# ForceAssistHandBrd.net
KiCad netlist of a schematic drawn in EAGLE
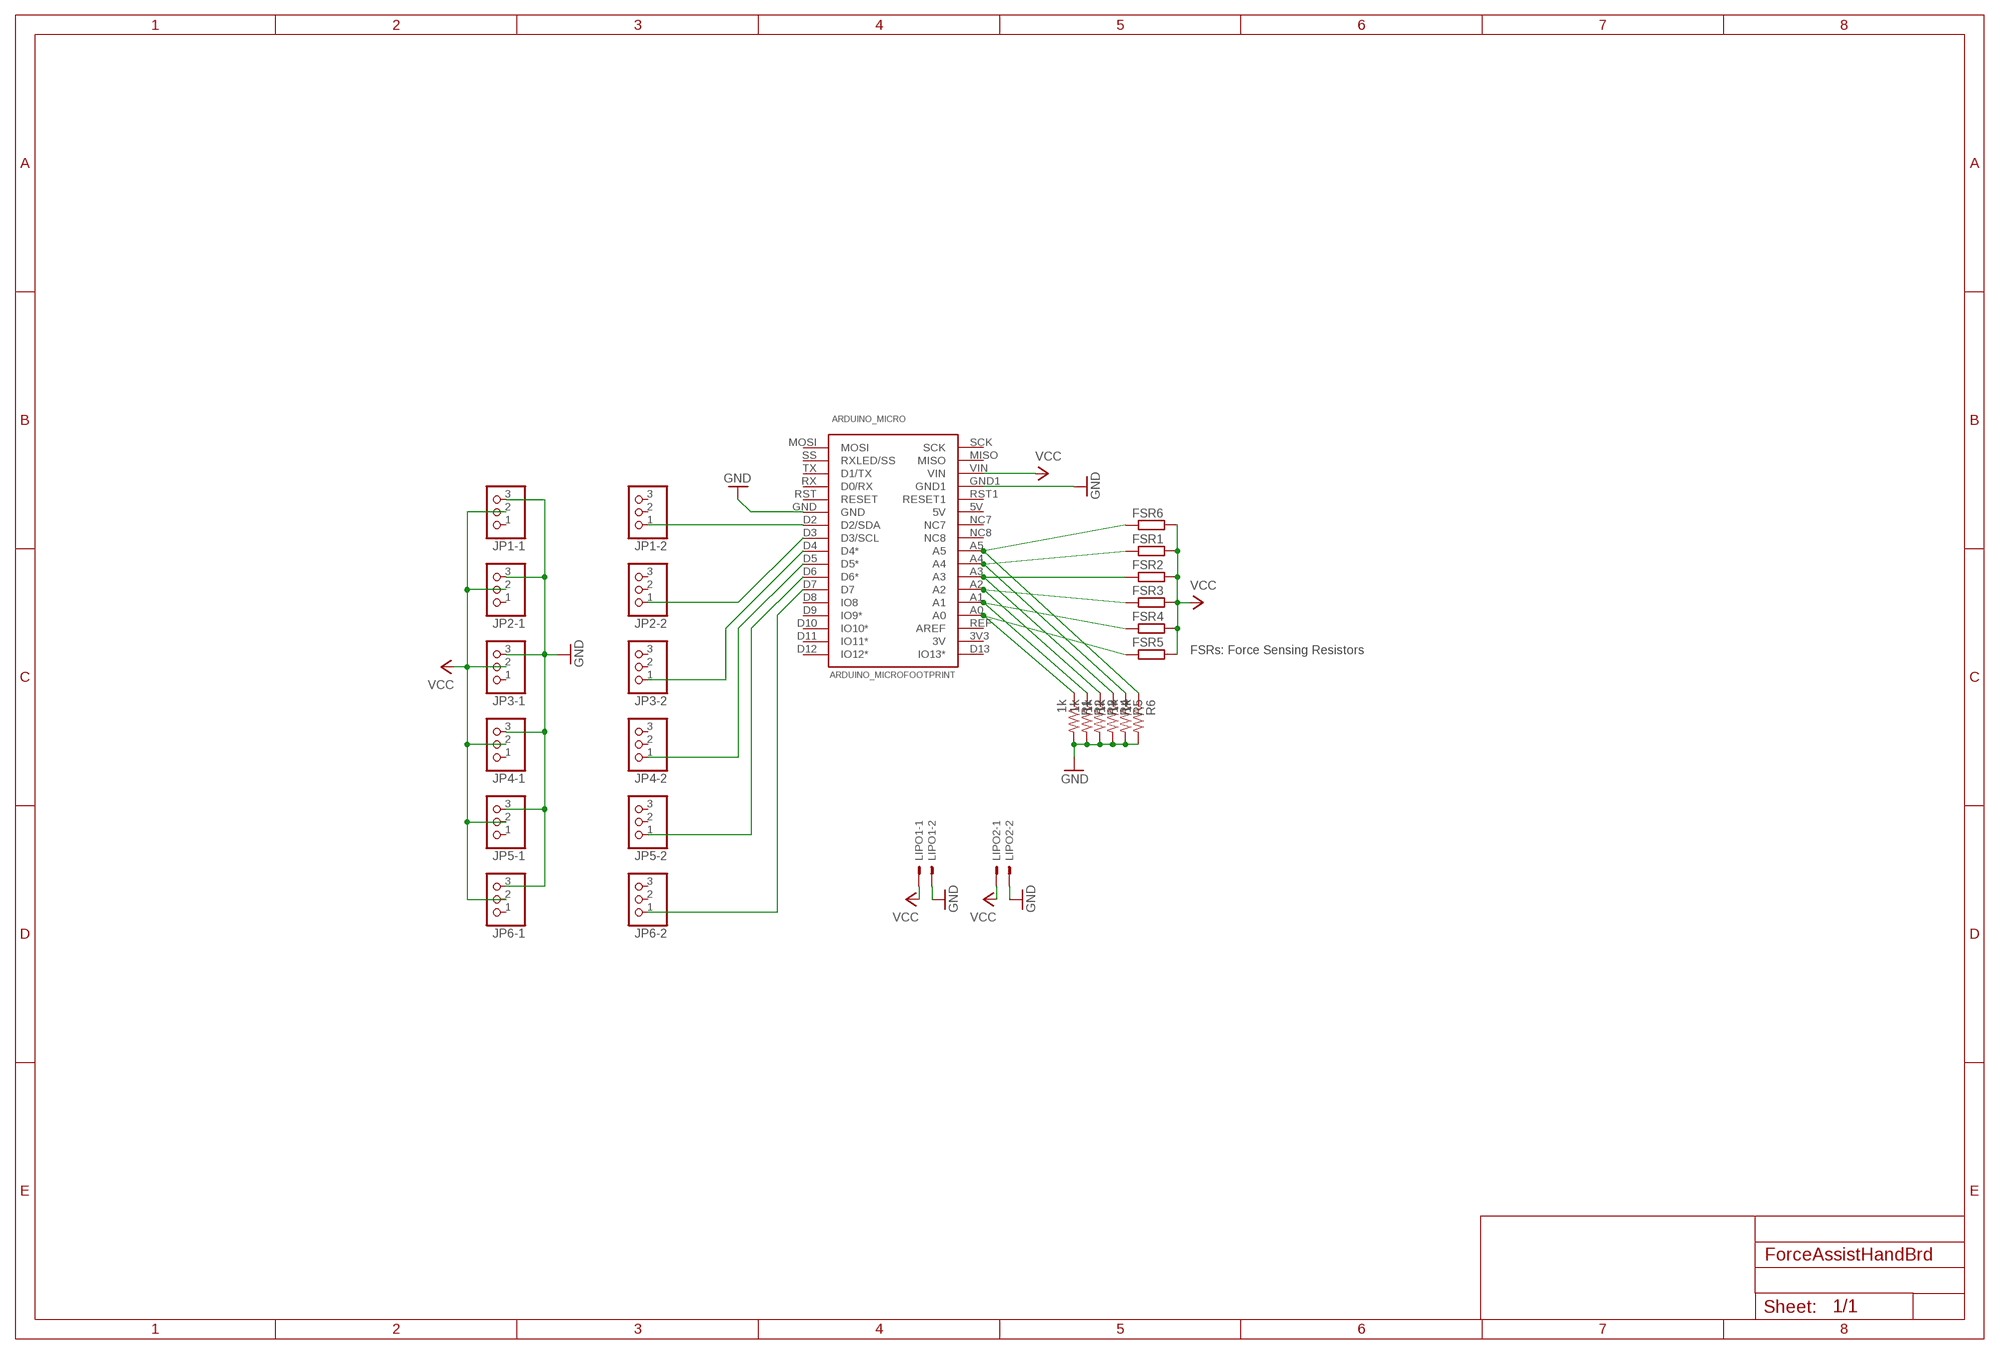
[diagram p0: schematic, sheet 1]

(export (version "E")
  (design (tool "Eeschema 10.0.6"))
  (components
    (comp (ref "ARDUINO_MICRO")
      (value "ARDUINO_MICROFOOTPRINT")
      (footprint "eagle-import:ARDUINO-MICRO")
      (libsource (lib "eagle-import") (part "ARDUINO_MICROFOOTPRINT"))
    )
    (comp (ref "FSR1")
      (value "R-EU_0204/2V")
      (footprint "eagle-import:0204V")
      (libsource (lib "eagle-import") (part "R-EU_0204/2V"))
    )
    (comp (ref "FSR2")
      (value "R-EU_0204/2V")
      (footprint "eagle-import:0204V")
      (libsource (lib "eagle-import") (part "R-EU_0204/2V"))
    )
    (comp (ref "FSR3")
      (value "R-EU_0204/2V")
      (footprint "eagle-import:0204V")
      (libsource (lib "eagle-import") (part "R-EU_0204/2V"))
    )
    (comp (ref "FSR4")
      (value "R-EU_0204/2V")
      (footprint "eagle-import:0204V")
      (libsource (lib "eagle-import") (part "R-EU_0204/2V"))
    )
    (comp (ref "FSR5")
      (value "R-EU_0204/2V")
      (footprint "eagle-import:0204V")
      (libsource (lib "eagle-import") (part "R-EU_0204/2V"))
    )
    (comp (ref "FSR6")
      (value "R-EU_0204/2V")
      (footprint "eagle-import:0204V")
      (libsource (lib "eagle-import") (part "R-EU_0204/2V"))
    )
    (comp (ref "JP1-1")
      (value "PINHD-1X3")
      (footprint "eagle-import:1X03")
      (libsource (lib "eagle-import") (part "PINHD-1X3"))
    )
    (comp (ref "JP1-2")
      (value "PINHD-1X3")
      (footprint "eagle-import:1X03")
      (libsource (lib "eagle-import") (part "PINHD-1X3"))
    )
    (comp (ref "JP2-1")
      (value "PINHD-1X3")
      (footprint "eagle-import:1X03")
      (libsource (lib "eagle-import") (part "PINHD-1X3"))
    )
    (comp (ref "JP2-2")
      (value "PINHD-1X3")
      (footprint "eagle-import:1X03")
      (libsource (lib "eagle-import") (part "PINHD-1X3"))
    )
    (comp (ref "JP3-1")
      (value "PINHD-1X3")
      (footprint "eagle-import:1X03")
      (libsource (lib "eagle-import") (part "PINHD-1X3"))
    )
    (comp (ref "JP3-2")
      (value "PINHD-1X3")
      (footprint "eagle-import:1X03")
      (libsource (lib "eagle-import") (part "PINHD-1X3"))
    )
    (comp (ref "JP4-1")
      (value "PINHD-1X3")
      (footprint "eagle-import:1X03")
      (libsource (lib "eagle-import") (part "PINHD-1X3"))
    )
    (comp (ref "JP4-2")
      (value "PINHD-1X3")
      (footprint "eagle-import:1X03")
      (libsource (lib "eagle-import") (part "PINHD-1X3"))
    )
    (comp (ref "JP5-1")
      (value "PINHD-1X3")
      (footprint "eagle-import:1X03")
      (libsource (lib "eagle-import") (part "PINHD-1X3"))
    )
    (comp (ref "JP5-2")
      (value "PINHD-1X3")
      (footprint "eagle-import:1X03")
      (libsource (lib "eagle-import") (part "PINHD-1X3"))
    )
    (comp (ref "JP6-1")
      (value "PINHD-1X3")
      (footprint "eagle-import:1X03")
      (libsource (lib "eagle-import") (part "PINHD-1X3"))
    )
    (comp (ref "JP6-2")
      (value "PINHD-1X3")
      (footprint "eagle-import:1X03")
      (libsource (lib "eagle-import") (part "PINHD-1X3"))
    )
    (comp (ref "LIPO1")
      (value "22-23-2021")
      (footprint "eagle-import:22-23-2021")
      (fields (field (name "MF") "MOLEX"))
      (libsource (lib "eagle-import") (part "22-23-2021"))
    )
    (comp (ref "LIPO2")
      (value "22-23-2021")
      (footprint "eagle-import:22-23-2021")
      (fields (field (name "MF") "MOLEX"))
      (libsource (lib "eagle-import") (part "22-23-2021"))
    )
    (comp (ref "R1")
      (value "1k")
      (footprint "eagle-import:0204_7")
      (libsource (lib "eagle-import") (part "R-US_0204/7"))
    )
    (comp (ref "R2")
      (value "1k")
      (footprint "eagle-import:0204_7")
      (libsource (lib "eagle-import") (part "R-US_0204/7"))
    )
    (comp (ref "R3")
      (value "1k")
      (footprint "eagle-import:0204_7")
      (libsource (lib "eagle-import") (part "R-US_0204/7"))
    )
    (comp (ref "R4")
      (value "1k")
      (footprint "eagle-import:0204_7")
      (libsource (lib "eagle-import") (part "R-US_0204/7"))
    )
    (comp (ref "R5")
      (value "1k")
      (footprint "eagle-import:0204_7")
      (libsource (lib "eagle-import") (part "R-US_0204/7"))
    )
    (comp (ref "R6")
      (value "1k")
      (footprint "eagle-import:0204_7")
      (libsource (lib "eagle-import") (part "R-US_0204/7"))
    )
  )
  (nets
    (net (code "1") (name "GND") (class "Default")
      (node (ref "ARDUINO_MICRO") (pin "GND") (pinfunction "GND_GND") (pintype "bidirectional"))
      (node (ref "ARDUINO_MICRO") (pin "GND1") (pinfunction "GND1_GND1") (pintype "bidirectional"))
      (node (ref "JP1-1") (pin "3") (pinfunction "3_3") (pintype "passive"))
      (node (ref "JP2-1") (pin "3") (pinfunction "3_3") (pintype "passive"))
      (node (ref "JP3-1") (pin "3") (pinfunction "3_3") (pintype "passive"))
      (node (ref "JP4-1") (pin "3") (pinfunction "3_3") (pintype "passive"))
      (node (ref "JP5-1") (pin "3") (pinfunction "3_3") (pintype "passive"))
      (node (ref "JP6-1") (pin "3") (pinfunction "3_3") (pintype "passive"))
      (node (ref "LIPO1") (pin "2") (pinfunction "S_2") (pintype "passive"))
      (node (ref "LIPO2") (pin "2") (pinfunction "S_2") (pintype "passive"))
      (node (ref "R1") (pin "2") (pinfunction "2_2") (pintype "passive"))
      (node (ref "R2") (pin "2") (pinfunction "2_2") (pintype "passive"))
      (node (ref "R3") (pin "2") (pinfunction "2_2") (pintype "passive"))
      (node (ref "R4") (pin "2") (pinfunction "2_2") (pintype "passive"))
      (node (ref "R5") (pin "2") (pinfunction "2_2") (pintype "passive"))
      (node (ref "R6") (pin "2") (pinfunction "2_2") (pintype "passive"))
    )
    (net (code "2") (name "Net-(ARDUINO_MICRO-D2{slash}SDA)") (class "Default")
      (node (ref "ARDUINO_MICRO") (pin "D2") (pinfunction "D2/SDA_D2") (pintype "bidirectional"))
      (node (ref "JP1-2") (pin "1") (pinfunction "1_1") (pintype "passive"))
    )
    (net (code "3") (name "Net-(ARDUINO_MICRO-D3{slash}SCL)") (class "Default")
      (node (ref "ARDUINO_MICRO") (pin "D3") (pinfunction "D3/SCL_D3") (pintype "bidirectional"))
      (node (ref "JP2-2") (pin "1") (pinfunction "1_1") (pintype "passive"))
    )
    (net (code "4") (name "Net-(ARDUINO_MICRO-D4*)") (class "Default")
      (node (ref "ARDUINO_MICRO") (pin "D4") (pinfunction "D4*_D4") (pintype "bidirectional"))
      (node (ref "JP3-2") (pin "1") (pinfunction "1_1") (pintype "passive"))
    )
    (net (code "5") (name "Net-(ARDUINO_MICRO-D5*)") (class "Default")
      (node (ref "ARDUINO_MICRO") (pin "D5") (pinfunction "D5*_D5") (pintype "bidirectional"))
      (node (ref "JP4-2") (pin "1") (pinfunction "1_1") (pintype "passive"))
    )
    (net (code "6") (name "Net-(ARDUINO_MICRO-D6*)") (class "Default")
      (node (ref "ARDUINO_MICRO") (pin "D6") (pinfunction "D6*_D6") (pintype "bidirectional"))
      (node (ref "JP5-2") (pin "1") (pinfunction "1_1") (pintype "passive"))
    )
    (net (code "7") (name "Net-(ARDUINO_MICRO-PadA0)") (class "Default")
      (node (ref "ARDUINO_MICRO") (pin "A0") (pinfunction "A0_A0") (pintype "bidirectional"))
      (node (ref "FSR5") (pin "1") (pinfunction "1_1") (pintype "passive"))
      (node (ref "R1") (pin "1") (pinfunction "1_1") (pintype "passive"))
    )
    (net (code "8") (name "Net-(ARDUINO_MICRO-PadA1)") (class "Default")
      (node (ref "ARDUINO_MICRO") (pin "A1") (pinfunction "A1_A1") (pintype "bidirectional"))
      (node (ref "FSR4") (pin "1") (pinfunction "1_1") (pintype "passive"))
      (node (ref "R2") (pin "1") (pinfunction "1_1") (pintype "passive"))
    )
    (net (code "9") (name "Net-(ARDUINO_MICRO-PadA2)") (class "Default")
      (node (ref "ARDUINO_MICRO") (pin "A2") (pinfunction "A2_A2") (pintype "bidirectional"))
      (node (ref "FSR3") (pin "1") (pinfunction "1_1") (pintype "passive"))
      (node (ref "R3") (pin "1") (pinfunction "1_1") (pintype "passive"))
    )
    (net (code "10") (name "Net-(ARDUINO_MICRO-PadA3)") (class "Default")
      (node (ref "ARDUINO_MICRO") (pin "A3") (pinfunction "A3_A3") (pintype "bidirectional"))
      (node (ref "FSR2") (pin "1") (pinfunction "1_1") (pintype "passive"))
      (node (ref "R4") (pin "1") (pinfunction "1_1") (pintype "passive"))
    )
    (net (code "11") (name "Net-(ARDUINO_MICRO-PadA4)") (class "Default")
      (node (ref "ARDUINO_MICRO") (pin "A4") (pinfunction "A4_A4") (pintype "bidirectional"))
      (node (ref "FSR1") (pin "1") (pinfunction "1_1") (pintype "passive"))
      (node (ref "R5") (pin "1") (pinfunction "1_1") (pintype "passive"))
    )
    (net (code "12") (name "Net-(ARDUINO_MICRO-PadA5)") (class "Default")
      (node (ref "ARDUINO_MICRO") (pin "A5") (pinfunction "A5_A5") (pintype "bidirectional"))
      (node (ref "FSR6") (pin "1") (pinfunction "1_1") (pintype "passive"))
      (node (ref "R6") (pin "1") (pinfunction "1_1") (pintype "passive"))
    )
    (net (code "13") (name "Net-(ARDUINO_MICRO-PadD7)") (class "Default")
      (node (ref "ARDUINO_MICRO") (pin "D7") (pinfunction "D7_D7") (pintype "bidirectional"))
      (node (ref "JP6-2") (pin "1") (pinfunction "1_1") (pintype "passive"))
    )
    (net (code "14") (name "VCC") (class "Default")
      (node (ref "ARDUINO_MICRO") (pin "VIN") (pinfunction "VIN_VIN") (pintype "bidirectional"))
      (node (ref "FSR1") (pin "2") (pinfunction "2_2") (pintype "passive"))
      (node (ref "FSR2") (pin "2") (pinfunction "2_2") (pintype "passive"))
      (node (ref "FSR3") (pin "2") (pinfunction "2_2") (pintype "passive"))
      (node (ref "FSR4") (pin "2") (pinfunction "2_2") (pintype "passive"))
      (node (ref "FSR5") (pin "2") (pinfunction "2_2") (pintype "passive"))
      (node (ref "FSR6") (pin "2") (pinfunction "2_2") (pintype "passive"))
      (node (ref "JP1-1") (pin "2") (pinfunction "2_2") (pintype "passive"))
      (node (ref "JP2-1") (pin "2") (pinfunction "2_2") (pintype "passive"))
      (node (ref "JP3-1") (pin "2") (pinfunction "2_2") (pintype "passive"))
      (node (ref "JP4-1") (pin "2") (pinfunction "2_2") (pintype "passive"))
      (node (ref "JP5-1") (pin "2") (pinfunction "2_2") (pintype "passive"))
      (node (ref "JP6-1") (pin "2") (pinfunction "2_2") (pintype "passive"))
      (node (ref "LIPO1") (pin "1") (pinfunction "S_1") (pintype "passive"))
      (node (ref "LIPO2") (pin "1") (pinfunction "S_1") (pintype "passive"))
    )
    (net (code "15") (name "unconnected-(ARDUINO_MICRO-3V-Pad3V3)") (class "Default")
      (node (ref "ARDUINO_MICRO") (pin "3V3") (pinfunction "3V_3V3") (pintype "bidirectional"))
    )
    (net (code "16") (name "unconnected-(ARDUINO_MICRO-AREF-PadREF)") (class "Default")
      (node (ref "ARDUINO_MICRO") (pin "REF") (pinfunction "AREF_REF") (pintype "bidirectional"))
    )
    (net (code "17") (name "unconnected-(ARDUINO_MICRO-D0{slash}RX-PadRX)") (class "Default")
      (node (ref "ARDUINO_MICRO") (pin "RX") (pinfunction "D0/RX_RX") (pintype "bidirectional"))
    )
    (net (code "18") (name "unconnected-(ARDUINO_MICRO-D1{slash}TX-PadTX)") (class "Default")
      (node (ref "ARDUINO_MICRO") (pin "TX") (pinfunction "D1/TX_TX") (pintype "bidirectional"))
    )
    (net (code "19") (name "unconnected-(ARDUINO_MICRO-IO8-PadD8)") (class "Default")
      (node (ref "ARDUINO_MICRO") (pin "D8") (pinfunction "IO8_D8") (pintype "bidirectional"))
    )
    (net (code "20") (name "unconnected-(ARDUINO_MICRO-IO9*-PadD9)") (class "Default")
      (node (ref "ARDUINO_MICRO") (pin "D9") (pinfunction "IO9*_D9") (pintype "bidirectional"))
    )
    (net (code "21") (name "unconnected-(ARDUINO_MICRO-IO10*-PadD10)") (class "Default")
      (node (ref "ARDUINO_MICRO") (pin "D10") (pinfunction "IO10*_D10") (pintype "bidirectional"))
    )
    (net (code "22") (name "unconnected-(ARDUINO_MICRO-IO11*-PadD11)") (class "Default")
      (node (ref "ARDUINO_MICRO") (pin "D11") (pinfunction "IO11*_D11") (pintype "bidirectional"))
    )
    (net (code "23") (name "unconnected-(ARDUINO_MICRO-IO12*-PadD12)") (class "Default")
      (node (ref "ARDUINO_MICRO") (pin "D12") (pinfunction "IO12*_D12") (pintype "bidirectional"))
    )
    (net (code "24") (name "unconnected-(ARDUINO_MICRO-IO13*-PadD13)") (class "Default")
      (node (ref "ARDUINO_MICRO") (pin "D13") (pinfunction "IO13*_D13") (pintype "bidirectional"))
    )
    (net (code "25") (name "unconnected-(ARDUINO_MICRO-Pad5V)") (class "Default")
      (node (ref "ARDUINO_MICRO") (pin "5V") (pinfunction "5V_5V") (pintype "bidirectional"))
    )
    (net (code "26") (name "unconnected-(ARDUINO_MICRO-PadMISO)") (class "Default")
      (node (ref "ARDUINO_MICRO") (pin "MISO") (pinfunction "MISO_MISO") (pintype "bidirectional"))
    )
    (net (code "27") (name "unconnected-(ARDUINO_MICRO-PadMOSI)") (class "Default")
      (node (ref "ARDUINO_MICRO") (pin "MOSI") (pinfunction "MOSI_MOSI") (pintype "bidirectional"))
    )
    (net (code "28") (name "unconnected-(ARDUINO_MICRO-PadNC7)") (class "Default")
      (node (ref "ARDUINO_MICRO") (pin "NC7") (pinfunction "NC7_NC7") (pintype "bidirectional"))
    )
    (net (code "29") (name "unconnected-(ARDUINO_MICRO-PadNC8)") (class "Default")
      (node (ref "ARDUINO_MICRO") (pin "NC8") (pinfunction "NC8_NC8") (pintype "bidirectional"))
    )
    (net (code "30") (name "unconnected-(ARDUINO_MICRO-PadSCK)") (class "Default")
      (node (ref "ARDUINO_MICRO") (pin "SCK") (pinfunction "SCK_SCK") (pintype "bidirectional"))
    )
    (net (code "31") (name "unconnected-(ARDUINO_MICRO-RESET-PadRST)") (class "Default")
      (node (ref "ARDUINO_MICRO") (pin "RST") (pinfunction "RESET_RST") (pintype "bidirectional"))
    )
    (net (code "32") (name "unconnected-(ARDUINO_MICRO-RESET1-PadRST1)") (class "Default")
      (node (ref "ARDUINO_MICRO") (pin "RST1") (pinfunction "RESET1_RST1") (pintype "bidirectional"))
    )
    (net (code "33") (name "unconnected-(ARDUINO_MICRO-RXLED{slash}SS-PadSS)") (class "Default")
      (node (ref "ARDUINO_MICRO") (pin "SS") (pinfunction "RXLED/SS_SS") (pintype "bidirectional"))
    )
    (net (code "34") (name "unconnected-(JP1-1-Pad1)") (class "Default")
      (node (ref "JP1-1") (pin "1") (pinfunction "1_1") (pintype "passive"))
    )
    (net (code "35") (name "unconnected-(JP1-2-Pad2)") (class "Default")
      (node (ref "JP1-2") (pin "2") (pinfunction "2_2") (pintype "passive"))
    )
    (net (code "36") (name "unconnected-(JP1-2-Pad3)") (class "Default")
      (node (ref "JP1-2") (pin "3") (pinfunction "3_3") (pintype "passive"))
    )
    (net (code "37") (name "unconnected-(JP2-1-Pad1)") (class "Default")
      (node (ref "JP2-1") (pin "1") (pinfunction "1_1") (pintype "passive"))
    )
    (net (code "38") (name "unconnected-(JP2-2-Pad2)") (class "Default")
      (node (ref "JP2-2") (pin "2") (pinfunction "2_2") (pintype "passive"))
    )
    (net (code "39") (name "unconnected-(JP2-2-Pad3)") (class "Default")
      (node (ref "JP2-2") (pin "3") (pinfunction "3_3") (pintype "passive"))
    )
    (net (code "40") (name "unconnected-(JP3-1-Pad1)") (class "Default")
      (node (ref "JP3-1") (pin "1") (pinfunction "1_1") (pintype "passive"))
    )
    (net (code "41") (name "unconnected-(JP3-2-Pad2)") (class "Default")
      (node (ref "JP3-2") (pin "2") (pinfunction "2_2") (pintype "passive"))
    )
    (net (code "42") (name "unconnected-(JP3-2-Pad3)") (class "Default")
      (node (ref "JP3-2") (pin "3") (pinfunction "3_3") (pintype "passive"))
    )
    (net (code "43") (name "unconnected-(JP4-1-Pad1)") (class "Default")
      (node (ref "JP4-1") (pin "1") (pinfunction "1_1") (pintype "passive"))
    )
    (net (code "44") (name "unconnected-(JP4-2-Pad2)") (class "Default")
      (node (ref "JP4-2") (pin "2") (pinfunction "2_2") (pintype "passive"))
    )
    (net (code "45") (name "unconnected-(JP4-2-Pad3)") (class "Default")
      (node (ref "JP4-2") (pin "3") (pinfunction "3_3") (pintype "passive"))
    )
    (net (code "46") (name "unconnected-(JP5-1-Pad1)") (class "Default")
      (node (ref "JP5-1") (pin "1") (pinfunction "1_1") (pintype "passive"))
    )
    (net (code "47") (name "unconnected-(JP5-2-Pad2)") (class "Default")
      (node (ref "JP5-2") (pin "2") (pinfunction "2_2") (pintype "passive"))
    )
    (net (code "48") (name "unconnected-(JP5-2-Pad3)") (class "Default")
      (node (ref "JP5-2") (pin "3") (pinfunction "3_3") (pintype "passive"))
    )
    (net (code "49") (name "unconnected-(JP6-1-Pad1)") (class "Default")
      (node (ref "JP6-1") (pin "1") (pinfunction "1_1") (pintype "passive"))
    )
    (net (code "50") (name "unconnected-(JP6-2-Pad2)") (class "Default")
      (node (ref "JP6-2") (pin "2") (pinfunction "2_2") (pintype "passive"))
    )
    (net (code "51") (name "unconnected-(JP6-2-Pad3)") (class "Default")
      (node (ref "JP6-2") (pin "3") (pinfunction "3_3") (pintype "passive"))
    )
  )
)
